# ArbPwrBoost_P3.net
KiCad netlist of a schematic drawn in Altium Designer
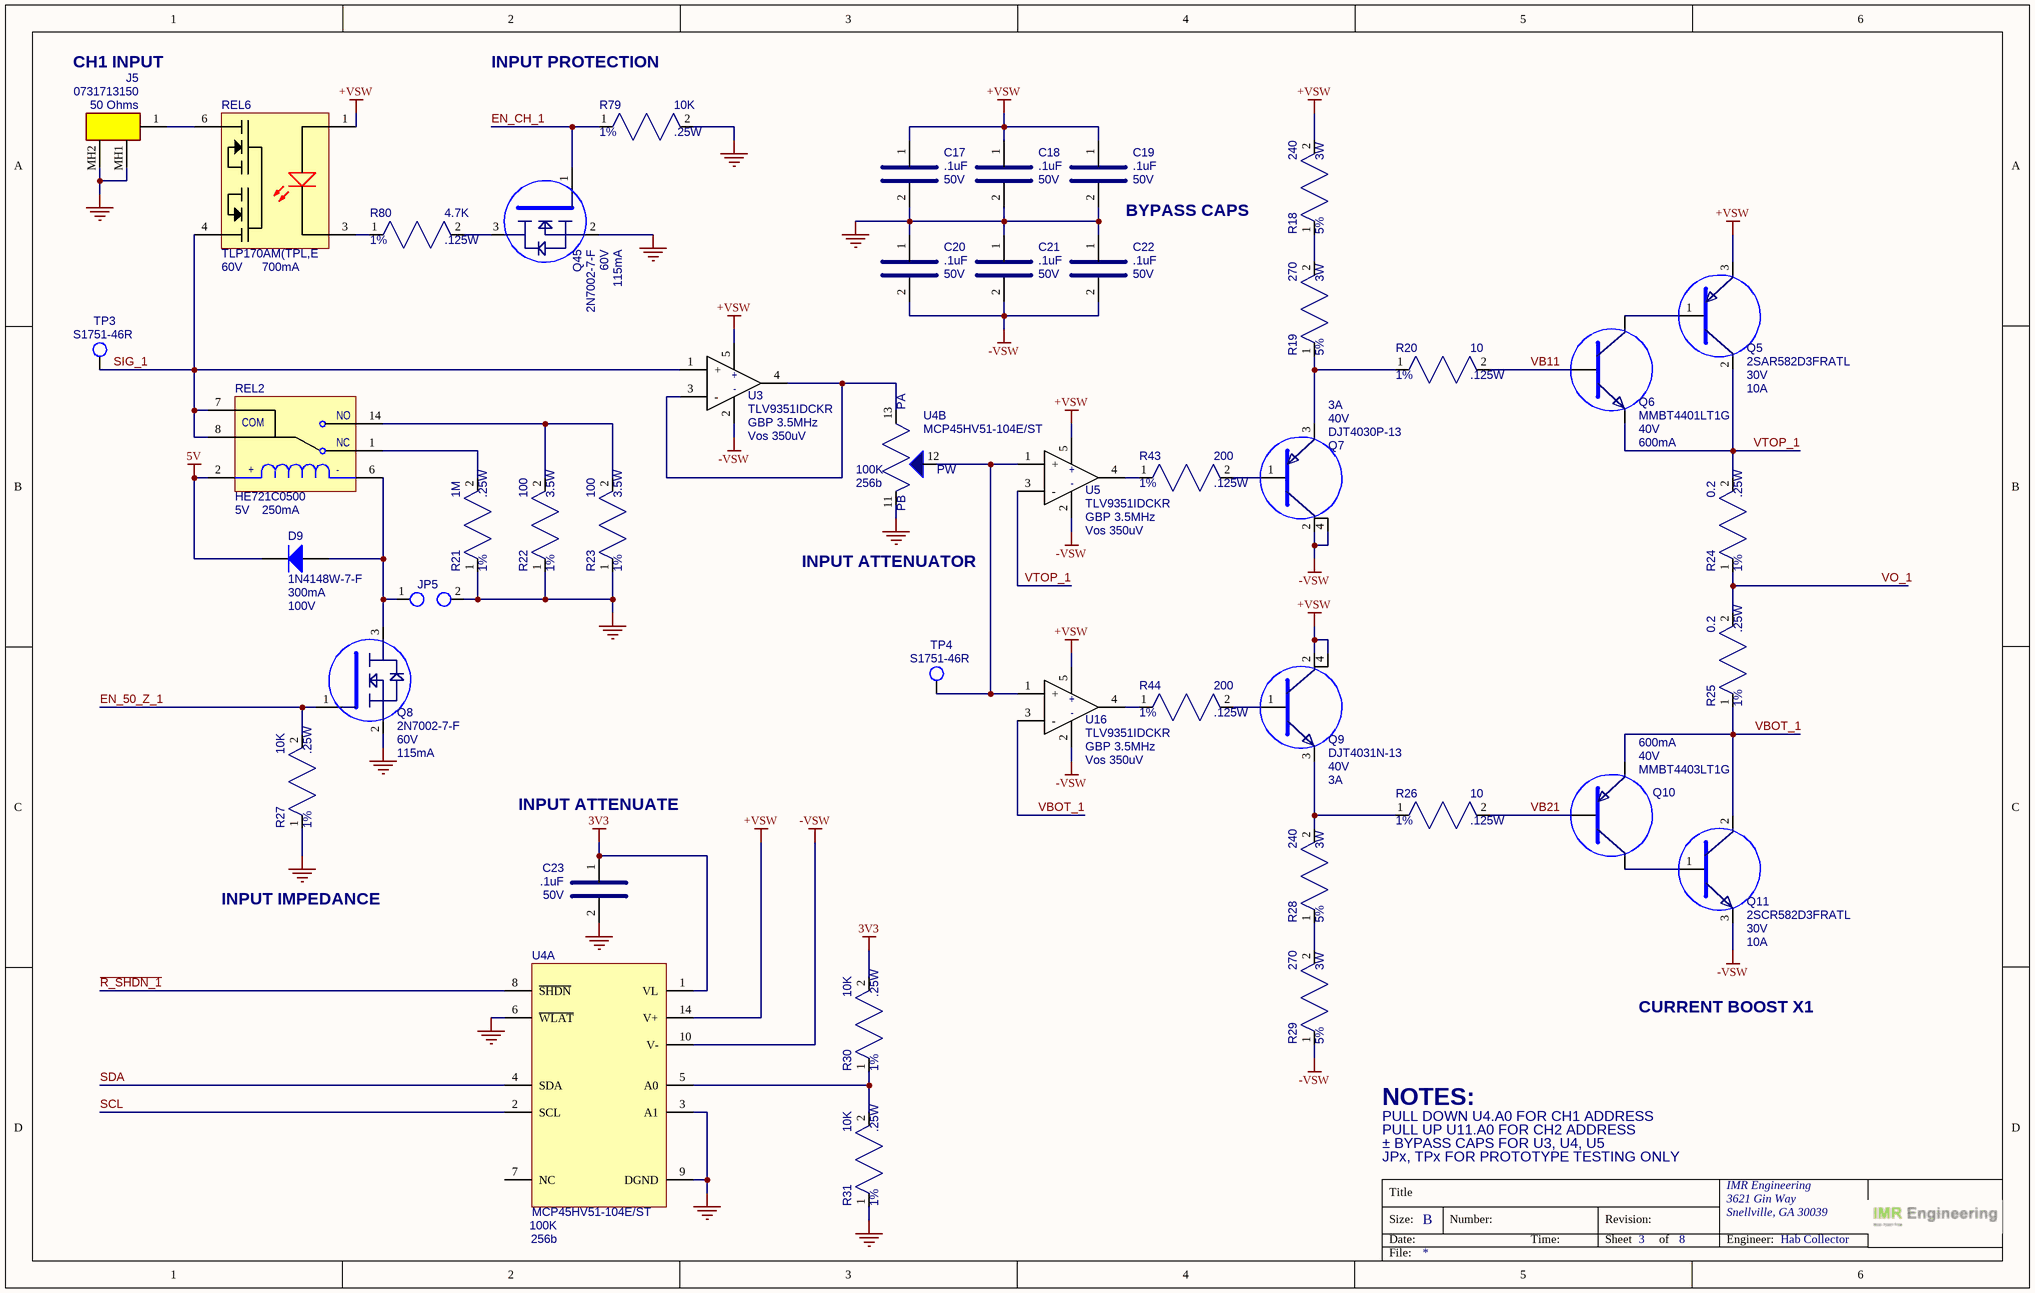
[diagram p0: ArbPwrBoost_P3.SchDoc]

(export (version "E")
  (design (tool "Eeschema 10.0.6"))
  (components
    (comp (ref "C17")
      (value ".1uF")
      (footprint "CAP_0805")
      (description "CAP CER 0.1UF 50V X7R 0805")
      (fields
        (field (name "MFG") "KYOCERA AVX")
        (field (name "VOLTAGE") "50V")
        (field (name "Comment") "KGM21NR71H104KT")
      )
      (libsource (lib "IMR_LIB_SCH_R2") (part "CAP_SMD_0.1UF_50V_0805"))
    )
    (comp (ref "C18")
      (value ".1uF")
      (footprint "CAP_0805")
      (description "CAP CER 0.1UF 50V X7R 0805")
      (fields
        (field (name "MFG") "KYOCERA AVX")
        (field (name "VOLTAGE") "50V")
        (field (name "Comment") "KGM21NR71H104KT")
      )
      (libsource (lib "IMR_LIB_SCH_R2") (part "CAP_SMD_0.1UF_50V_0805"))
    )
    (comp (ref "C19")
      (value ".1uF")
      (footprint "CAP_0805")
      (description "CAP CER 0.1UF 50V X7R 0805")
      (fields
        (field (name "MFG") "KYOCERA AVX")
        (field (name "VOLTAGE") "50V")
        (field (name "Comment") "KGM21NR71H104KT")
      )
      (libsource (lib "IMR_LIB_SCH_R2") (part "CAP_SMD_0.1UF_50V_0805"))
    )
    (comp (ref "C20")
      (value ".1uF")
      (footprint "CAP_0805")
      (description "CAP CER 0.1UF 50V X7R 0805")
      (fields
        (field (name "MFG") "KYOCERA AVX")
        (field (name "VOLTAGE") "50V")
        (field (name "Comment") "KGM21NR71H104KT")
      )
      (libsource (lib "IMR_LIB_SCH_R2") (part "CAP_SMD_0.1UF_50V_0805"))
    )
    (comp (ref "C21")
      (value ".1uF")
      (footprint "CAP_0805")
      (description "CAP CER 0.1UF 50V X7R 0805")
      (fields
        (field (name "MFG") "KYOCERA AVX")
        (field (name "VOLTAGE") "50V")
        (field (name "Comment") "KGM21NR71H104KT")
      )
      (libsource (lib "IMR_LIB_SCH_R2") (part "CAP_SMD_0.1UF_50V_0805"))
    )
    (comp (ref "C22")
      (value ".1uF")
      (footprint "CAP_0805")
      (description "CAP CER 0.1UF 50V X7R 0805")
      (fields
        (field (name "MFG") "KYOCERA AVX")
        (field (name "VOLTAGE") "50V")
        (field (name "Comment") "KGM21NR71H104KT")
      )
      (libsource (lib "IMR_LIB_SCH_R2") (part "CAP_SMD_0.1UF_50V_0805"))
    )
    (comp (ref "C23")
      (value ".1uF")
      (footprint "CAP_0805")
      (description "CAP CER 0.1UF 50V X7R 0805")
      (fields
        (field (name "MFG") "KYOCERA AVX")
        (field (name "VOLTAGE") "50V")
        (field (name "Comment") "KGM21NR71H104KT")
      )
      (libsource (lib "IMR_LIB_SCH_R2") (part "CAP_SMD_0.1UF_50V_0805"))
    )
    (comp (ref "D9")
      (value "100V")
      (footprint "SOD123")
      (description "RELAY REED SPDT 250MA 5V")
      (fields
        (field (name "MFG") "Diodes Inc")
        (field (name "MFG_PN") "1N4148W-7-F")
        (field (name "CURRENT") "300mA")
        (field (name "Comment") "1N4148W-7-F")
      )
      (libsource (lib "IMR_LIB_SCH_R2") (part "DIODE_1N4148W-7-F"))
    )
    (comp (ref "J5")
      (value "50 Ohms")
      (footprint "731713150")
      (description "CONN BNC RCPT R/A 50 OHM PCB")
      (fields
        (field (name "MFG") "Molex")
        (field (name "MFG_PN") "0731713150")
        (field (name "Comment") "0731713150")
      )
      (libsource (lib "IMR_LIB_SCH_R2") (part "CONN_MOLEX_0731713150"))
    )
    (comp (ref "JP5")
      (value "PREC002SFAN-RC")
      (footprint "HDR_1X2_100MILL")
      (description "CONN HEADER VERT 2POS 2.54MM")
      (fields (field (name "MFG") "Sullins Connector Solutions"))
      (libsource (lib "IMR_LIB_SCH_R2") (part "CONN_JUMPER_2P_100MIL_VERT"))
    )
    (comp (ref "Q5")
      (value "30V")
      (footprint "TO-252")
      (description "TRANS PNP 30V 5.7A TO-252")
      (fields
        (field (name "MFG") "Rohm Semiconductor")
        (field (name "MFG_PN") "2SAR582D3FRATL")
        (field (name "CURRENT") "10A")
        (field (name "Comment") "2SAR582D3FRATL")
      )
      (libsource (lib "IMR_LIB_SCH_R2") (part "BJT_PNP_2SAR582D3FRATL"))
    )
    (comp (ref "Q6")
      (value "40V")
      (footprint "SOT-23")
      (description "TRANS NPN 40V 0.6A SOT23-3")
      (fields
        (field (name "MFG") "On Semiconductor")
        (field (name "MFG_PN") "MMBT4401LT1G")
        (field (name "CURRENT") "600mA")
        (field (name "Comment") "MMBT4401LT1G")
      )
      (libsource (lib "IMR_LIB_SCH_R2") (part "BJT_NPN_MMBT4401LT1G"))
    )
    (comp (ref "Q7")
      (value "40V")
      (footprint "SOT223")
      (description "TRANS PNP 40V 3A SOT223")
      (fields
        (field (name "MFG") "Diodes Inc")
        (field (name "MFG_PN") "DJT4030P-13")
        (field (name "CURRENT") "3A")
        (field (name "Comment") "DJT4030P-13")
      )
      (libsource (lib "IMR_LIB_SCH_R2") (part "BJT_PNP_DJT4030P-13"))
    )
    (comp (ref "Q8")
      (value "60V")
      (footprint "SOT-23")
      (description "MOSFET N-CH 60V 115MA SOT23-3")
      (fields
        (field (name "MFG") "Diodes Inc")
        (field (name "MFG_PN") "2N7002-7-F")
        (field (name "CURRENT") "115mA")
        (field (name "Comment") "2N7002-7-F")
      )
      (libsource (lib "") (part "MOSFET_NCH_2N7002-7-F_1"))
    )
    (comp (ref "Q9")
      (value "40V")
      (footprint "SOT223")
      (description "TRANS NPN 40V 3A SOT223")
      (fields
        (field (name "MFG") "Diodes Inc")
        (field (name "MFG_PN") "DJT4031N-13")
        (field (name "CURRENT") "3A")
        (field (name "Comment") "DJT4031N-13")
      )
      (libsource (lib "IMR_LIB_SCH_R2") (part "BJT_NPN_DJT4031N-13"))
    )
    (comp (ref "Q10")
      (value "40V")
      (footprint "SOT-23")
      (description "TRANS PNP 40V 0.6A SOT23-3")
      (fields
        (field (name "MFG") "On Semiconductor")
        (field (name "MFG_PN") "MMBT4403LT1G")
        (field (name "CURRENT") "600mA")
        (field (name "Comment") "MMBT4403LT1G")
      )
      (libsource (lib "IMR_LIB_SCH_R2") (part "BJT_PNP_MMBT4403LT1G"))
    )
    (comp (ref "Q11")
      (value "30V")
      (footprint "TO-252")
      (description "TRANS NPN 30V 10A TO-252")
      (fields
        (field (name "MFG") "Rohm Semiconductor")
        (field (name "MFG_PN") "2SCR582D3FRATL")
        (field (name "CURRENT") "10A")
        (field (name "Comment") "2SCR582D3FRATL")
      )
      (libsource (lib "IMR_LIB_SCH_R2") (part "BJT_NPN_2SCR582D3FRATL"))
    )
    (comp (ref "Q45")
      (value "60V")
      (footprint "SOT-23")
      (description "MOSFET N-CH 60V 115MA SOT23-3")
      (fields
        (field (name "MFG") "Diodes Inc")
        (field (name "MFG_PN") "2N7002-7-F")
        (field (name "CURRENT") "115mA")
        (field (name "Comment") "2N7002-7-F")
      )
      (libsource (lib "IMR_LIB_SCH_R2") (part "MOSFET_NCH_2N7002-7-F"))
    )
    (comp (ref "R18")
      (value "240")
      (footprint "RES_2512")
      (description "RES 240 OHM 5% 3W 2512")
      (fields
        (field (name "MFG") "Yageo")
        (field (name "POWER") "3W")
        (field (name "TOLERANCE") "5%")
        (field (name "Comment") "RC2512JK-07240RL")
      )
      (libsource (lib "IMR_LIB_SCH_R2") (part "RES_SMD_240_2512_3W_5%"))
    )
    (comp (ref "R19")
      (value "270")
      (footprint "RES_2512")
      (description "RES 270 OHM 5% 1W 2512")
      (fields
        (field (name "MFG") "Yageo")
        (field (name "POWER") "3W")
        (field (name "TOLERANCE") "5%")
        (field (name "Comment") "RC2512JK-07270RL")
      )
      (libsource (lib "IMR_LIB_SCH_R2") (part "RES_SMD_270_2512_3W_5%"))
    )
    (comp (ref "R20")
      (value "10")
      (footprint "RES_0805")
      (description "RES SMD 10 OHM 1% 1/8W 0805")
      (fields
        (field (name "MFG") "Yageo")
        (field (name "POWER") ".125W")
        (field (name "TOLERANCE") "1%")
        (field (name "Comment") "RC0805FR-1310RL")
      )
      (libsource (lib "IMR_LIB_SCH_R2") (part "RES_SMD_10_0805_1/8W_1%"))
    )
    (comp (ref "R21")
      (value "1M")
      (footprint "RES_0805")
      (description "RES SMD 1K OHM 1% 1/4W 0805")
      (fields
        (field (name "MFG") "Yageo")
        (field (name "POWER") ".25W")
        (field (name "TOLERANCE") "1%")
        (field (name "Comment") "RC0805FR-7W1ML")
      )
      (libsource (lib "IMR_LIB_SCH_R2") (part "RES_SMD_1M_0805_1/4W_1%"))
    )
    (comp (ref "R22")
      (value "100")
      (footprint "RES_2512")
      (description "RES SMD 100 OHM 1% 3.5W 2512")
      (fields
        (field (name "MFG") "Ohmite")
        (field (name "POWER") "3.5W")
        (field (name "TOLERANCE") "1%")
        (field (name "Comment") "ALN2512F100RE-1")
      )
      (libsource (lib "IMR_LIB_SCH_R2") (part "RES_SMD_100_0805_3.5W_1%"))
    )
    (comp (ref "R23")
      (value "100")
      (footprint "RES_2512")
      (description "RES SMD 100 OHM 1% 3.5W 2512")
      (fields
        (field (name "MFG") "Ohmite")
        (field (name "POWER") "3.5W")
        (field (name "TOLERANCE") "1%")
        (field (name "Comment") "ALN2512F100RE-1")
      )
      (libsource (lib "IMR_LIB_SCH_R2") (part "RES_SMD_100_0805_3.5W_1%"))
    )
    (comp (ref "R24")
      (value "0.2")
      (footprint "RES_1206")
      (description "RES SMD 0.2 OHM 1% 1/4W 1206")
      (fields
        (field (name "MFG") "Yageo")
        (field (name "POWER") ".25W")
        (field (name "TOLERANCE") "1%")
        (field (name "Comment") "RL1206FR-070R2L")
      )
      (libsource (lib "IMR_LIB_SCH_R2") (part "RES_SMD_0.2_1206_1/4W_1%"))
    )
    (comp (ref "R25")
      (value "0.2")
      (footprint "RES_1206")
      (description "RES SMD 0.2 OHM 1% 1/4W 1206")
      (fields
        (field (name "MFG") "Yageo")
        (field (name "POWER") ".25W")
        (field (name "TOLERANCE") "1%")
        (field (name "Comment") "RL1206FR-070R2L")
      )
      (libsource (lib "IMR_LIB_SCH_R2") (part "RES_SMD_0.2_1206_1/4W_1%"))
    )
    (comp (ref "R26")
      (value "10")
      (footprint "RES_0805")
      (description "RES SMD 10 OHM 1% 1/8W 0805")
      (fields
        (field (name "MFG") "Yageo")
        (field (name "POWER") ".125W")
        (field (name "TOLERANCE") "1%")
        (field (name "Comment") "RC0805FR-1310RL")
      )
      (libsource (lib "IMR_LIB_SCH_R2") (part "RES_SMD_10_0805_1/8W_1%"))
    )
    (comp (ref "R27")
      (value "10K")
      (footprint "RES_0805")
      (description "RES SMD 10K OHM 1% 1/4W 0805")
      (fields
        (field (name "MFG") "Yageo")
        (field (name "POWER") ".25W")
        (field (name "TOLERANCE") "1%")
        (field (name "Comment") "RC0805FR-7W10KL")
      )
      (libsource (lib "IMR_LIB_SCH_R2") (part "RES_SMD_10K_0805_1/4W_1%"))
    )
    (comp (ref "R28")
      (value "240")
      (footprint "RES_2512")
      (description "RES 240 OHM 5% 3W 2512")
      (fields
        (field (name "MFG") "Yageo")
        (field (name "POWER") "3W")
        (field (name "TOLERANCE") "5%")
        (field (name "Comment") "RC2512JK-07240RL")
      )
      (libsource (lib "IMR_LIB_SCH_R2") (part "RES_SMD_240_2512_3W_5%"))
    )
    (comp (ref "R29")
      (value "270")
      (footprint "RES_2512")
      (description "RES 270 OHM 5% 1W 2512")
      (fields
        (field (name "MFG") "Yageo")
        (field (name "POWER") "3W")
        (field (name "TOLERANCE") "5%")
        (field (name "Comment") "RC2512JK-07270RL")
      )
      (libsource (lib "IMR_LIB_SCH_R2") (part "RES_SMD_270_2512_3W_5%"))
    )
    (comp (ref "R30")
      (value "10K")
      (footprint "RES_0805")
      (description "RES SMD 10K OHM 1% 1/4W 0805")
      (fields
        (field (name "MFG") "Yageo")
        (field (name "POWER") ".25W")
        (field (name "TOLERANCE") "1%")
        (field (name "Comment") "RC0805FR-7W10KL")
      )
      (libsource (lib "IMR_LIB_SCH_R2") (part "RES_SMD_10K_0805_1/4W_1%"))
    )
    (comp (ref "R31")
      (value "10K")
      (footprint "RES_0805")
      (description "RES SMD 10K OHM 1% 1/4W 0805")
      (fields
        (field (name "MFG") "Yageo")
        (field (name "POWER") ".25W")
        (field (name "TOLERANCE") "1%")
        (field (name "Comment") "RC0805FR-7W10KL")
      )
      (libsource (lib "IMR_LIB_SCH_R2") (part "RES_SMD_10K_0805_1/4W_1%"))
    )
    (comp (ref "R43")
      (value "200")
      (footprint "RES_0805")
      (description "RES SMD 200 OHM 1% 1/8W 0805")
      (fields
        (field (name "MFG") "Yageo")
        (field (name "POWER") ".125W")
        (field (name "TOLERANCE") "1%")
        (field (name "Comment") "RC0805FR-07200RL")
      )
      (libsource (lib "IMR_LIB_SCH_R2") (part "RES_SMD_200_0805_1/8W_1%"))
    )
    (comp (ref "R44")
      (value "200")
      (footprint "RES_0805")
      (description "RES SMD 200 OHM 1% 1/8W 0805")
      (fields
        (field (name "MFG") "Yageo")
        (field (name "POWER") ".125W")
        (field (name "TOLERANCE") "1%")
        (field (name "Comment") "RC0805FR-07200RL")
      )
      (libsource (lib "IMR_LIB_SCH_R2") (part "RES_SMD_200_0805_1/8W_1%"))
    )
    (comp (ref "R79")
      (value "10K")
      (footprint "RES_0805")
      (description "RES SMD 10K OHM 1% 1/4W 0805")
      (fields
        (field (name "MFG") "Yageo")
        (field (name "POWER") ".25W")
        (field (name "TOLERANCE") "1%")
        (field (name "Comment") "RC0805FR-7W10KL")
      )
      (libsource (lib "IMR_LIB_SCH_R2") (part "RES_SMD_10K_0805_1/4W_1%"))
    )
    (comp (ref "R80")
      (value "4.7K")
      (footprint "RES_0805")
      (description "RES SMD 4.7K OHM 1% 1/8W 0805")
      (fields
        (field (name "MFG") "Yageo")
        (field (name "POWER") ".125W")
        (field (name "TOLERANCE") "1%")
        (field (name "Comment") "RC0805FR-134K7L")
      )
      (libsource (lib "IMR_LIB_SCH_R2") (part "RES_SMD_4.7K_0805_1/8W_1%"))
    )
    (comp (ref "REL2")
      (value "5V")
      (footprint "HE700")
      (description "RELAY REED SPDT 250MA 5V")
      (fields
        (field (name "MFG") "Littlefuse")
        (field (name "MFG_PN") "HE721C0500")
        (field (name "CURRENT") "250mA")
        (field (name "Comment") "HE721C0500")
      )
      (libsource (lib "IMR_LIB_SCH_R2") (part "RELAY_HE721C0500"))
    )
    (comp (ref "REL6")
      (value "60V")
      (footprint "SOP-6")
      (description "SSR RELAY SPST-NO 700MA 0-60V")
      (fields
        (field (name "MFG") "Toshiba")
        (field (name "MFG_PN") "TLP170AM(TPL,E")
        (field (name "CURRENT") "700mA")
        (field (name "Comment") "TLP170AM(TPL,E")
      )
      (libsource (lib "IMR_LIB_SCH_R2") (part "RELAY_TLP170AM(TPL,E"))
    )
    (comp (ref "TP3")
      (value "S1751-46R")
      (footprint "HARWIN_S1751")
      (description "PCB TEST POINT CONNECT")
      (fields (field (name "MFG") "Harwin Inc") (field (name "MFG_PN") "S1751-46R"))
      (libsource (lib "IMR_LIB_SCH_R2") (part "CONN_TEST_POINT_S1751-46R"))
    )
    (comp (ref "TP4")
      (value "S1751-46R")
      (footprint "HARWIN_S1751")
      (description "PCB TEST POINT CONNECT")
      (fields (field (name "MFG") "Harwin Inc") (field (name "MFG_PN") "S1751-46R"))
      (libsource (lib "IMR_LIB_SCH_R2") (part "CONN_TEST_POINT_S1751-46R"))
    )
    (comp (ref "U3")
      (value "GBP 3.5MHz")
      (footprint "SOT-353")
      (description "IC OPAMP GP 3.5MHZ 350uV C70-5")
      (fields
        (field (name "MFG") "Texas Instruments")
        (field (name "MFG_PN") "TLV9351IDCKR")
        (field (name "VOS") "Vos 350uV")
        (field (name "Comment") "TLV9351IDCKR")
      )
      (libsource (lib "IMR_LIB_SCH_R2") (part "OPAMP_TLV9351IDCKR"))
    )
    (comp (ref "U4")
      (value "100K")
      (footprint "TSSOP-14")
      (description "IC DGT POT 100KOHM 256TP 14TSSOP")
      (fields
        (field (name "MFG") "Microchip")
        (field (name "MFG_PN") "MCP45HV51-104E/ST")
        (field (name "TAP") "256b")
        (field (name "Comment") "MCP45HV51-104E/ST")
      )
      (libsource (lib "IMR_LIB_SCH_R2") (part "IC_MCP45HV51-104E/ST"))
    )
    (comp (ref "U5")
      (value "GBP 3.5MHz")
      (footprint "SOT-353")
      (description "IC OPAMP GP 3.5MHZ 350uV C70-5")
      (fields
        (field (name "MFG") "Texas Instruments")
        (field (name "MFG_PN") "TLV9351IDCKR")
        (field (name "VOS") "Vos 350uV")
        (field (name "Comment") "TLV9351IDCKR")
      )
      (libsource (lib "IMR_LIB_SCH_R2") (part "OPAMP_TLV9351IDCKR"))
    )
    (comp (ref "U16")
      (value "GBP 3.5MHz")
      (footprint "SOT-353")
      (description "IC OPAMP GP 3.5MHZ 350uV C70-5")
      (fields
        (field (name "MFG") "Texas Instruments")
        (field (name "MFG_PN") "TLV9351IDCKR")
        (field (name "VOS") "Vos 350uV")
        (field (name "Comment") "TLV9351IDCKR")
      )
      (libsource (lib "IMR_LIB_SCH_R2") (part "OPAMP_TLV9351IDCKR"))
    )
  )
  (nets
    (net (code "1") (name "+VSW") (class "Default")
      (node (ref "C17") (pin "1") (pinfunction "1_1") (pintype "passive"))
      (node (ref "C18") (pin "1") (pinfunction "1_1") (pintype "passive"))
      (node (ref "C19") (pin "1") (pinfunction "1_1") (pintype "passive"))
      (node (ref "Q5") (pin "3") (pinfunction "E_3") (pintype "passive"))
      (node (ref "Q9") (pin "2") (pinfunction "C_2") (pintype "passive"))
      (node (ref "Q9") (pin "4") (pinfunction "C_4") (pintype "passive"))
      (node (ref "R18") (pin "2") (pinfunction "2_2") (pintype "passive"))
      (node (ref "REL6") (pin "1") (pinfunction "1_1") (pintype "passive"))
      (node (ref "U16") (pin "5") (pintype "passive"))
      (node (ref "U3") (pin "5") (pintype "passive"))
      (node (ref "U4") (pin "14") (pinfunction "V+_14") (pintype "passive"))
      (node (ref "U5") (pin "5") (pintype "passive"))
    )
    (net (code "2") (name "-VSW") (class "Default")
      (node (ref "C20") (pin "2") (pinfunction "2_2") (pintype "passive"))
      (node (ref "C21") (pin "2") (pinfunction "2_2") (pintype "passive"))
      (node (ref "C22") (pin "2") (pinfunction "2_2") (pintype "passive"))
      (node (ref "Q11") (pin "3") (pinfunction "E_3") (pintype "passive"))
      (node (ref "Q7") (pin "2") (pinfunction "C_2") (pintype "passive"))
      (node (ref "Q7") (pin "4") (pinfunction "C_4") (pintype "passive"))
      (node (ref "R29") (pin "1") (pinfunction "1_1") (pintype "passive"))
      (node (ref "U16") (pin "2") (pintype "passive"))
      (node (ref "U3") (pin "2") (pintype "passive"))
      (node (ref "U4") (pin "10") (pinfunction "V-_10") (pintype "passive"))
      (node (ref "U5") (pin "2") (pintype "passive"))
    )
    (net (code "3") (name "/EN_50_Z_1") (class "Default")
      (node (ref "Q8") (pin "1") (pinfunction "B_1") (pintype "passive"))
      (node (ref "R27") (pin "2") (pinfunction "2_2") (pintype "passive"))
    )
    (net (code "4") (name "/EN_CH_1") (class "Default")
      (node (ref "Q45") (pin "1") (pinfunction "B_1") (pintype "passive"))
      (node (ref "R79") (pin "1") (pinfunction "1_1") (pintype "passive"))
    )
    (net (code "5") (name "/SCL") (class "Default")
      (node (ref "U4") (pin "2") (pinfunction "SCL_2") (pintype "passive"))
    )
    (net (code "6") (name "/SDA") (class "Default")
      (node (ref "U4") (pin "4") (pinfunction "SDA_4") (pintype "passive"))
    )
    (net (code "7") (name "/SIG_1") (class "Default")
      (node (ref "REL2") (pin "7") (pinfunction "COM_7") (pintype "passive"))
      (node (ref "REL2") (pin "8") (pinfunction "COM_8") (pintype "passive"))
      (node (ref "REL6") (pin "4") (pinfunction "4_4") (pintype "passive"))
      (node (ref "TP3") (pin "1") (pintype "passive"))
      (node (ref "U3") (pin "1") (pinfunction "+_1") (pintype "passive"))
    )
    (net (code "8") (name "/VB11") (class "Default")
      (node (ref "Q6") (pin "1") (pinfunction "B_1") (pintype "passive"))
      (node (ref "R20") (pin "2") (pinfunction "2_2") (pintype "passive"))
    )
    (net (code "9") (name "/VB21") (class "Default")
      (node (ref "Q10") (pin "1") (pinfunction "B_1") (pintype "passive"))
      (node (ref "R26") (pin "2") (pinfunction "2_2") (pintype "passive"))
    )
    (net (code "10") (name "/VBOT_1") (class "Default")
      (node (ref "Q10") (pin "2") (pinfunction "E_2") (pintype "passive"))
      (node (ref "Q11") (pin "2") (pinfunction "C_2") (pintype "passive"))
      (node (ref "R25") (pin "1") (pinfunction "1_1") (pintype "passive"))
      (node (ref "U16") (pin "3") (pinfunction "-_3") (pintype "passive"))
    )
    (net (code "11") (name "/VO_1") (class "Default")
      (node (ref "R24") (pin "1") (pinfunction "1_1") (pintype "passive"))
      (node (ref "R25") (pin "2") (pinfunction "2_2") (pintype "passive"))
    )
    (net (code "12") (name "/VTOP_1") (class "Default")
      (node (ref "Q5") (pin "2") (pinfunction "C_2") (pintype "passive"))
      (node (ref "Q6") (pin "2") (pinfunction "E_2") (pintype "passive"))
      (node (ref "R24") (pin "2") (pinfunction "2_2") (pintype "passive"))
      (node (ref "U5") (pin "3") (pinfunction "-_3") (pintype "passive"))
    )
    (net (code "13") (name "/~{R_SHDN_1}") (class "Default")
      (node (ref "U4") (pin "8") (pinfunction "~{SHDN}_8") (pintype "passive"))
    )
    (net (code "14") (name "3V3") (class "Default")
      (node (ref "C23") (pin "1") (pinfunction "1_1") (pintype "passive"))
      (node (ref "R30") (pin "2") (pinfunction "2_2") (pintype "passive"))
      (node (ref "U4") (pin "1") (pinfunction "VL_1") (pintype "passive"))
    )
    (net (code "15") (name "5V") (class "Default")
      (node (ref "D9") (pin "2") (pinfunction "K_2") (pintype "passive"))
      (node (ref "REL2") (pin "2") (pintype "passive"))
    )
    (net (code "16") (name "GND") (class "Default")
      (node (ref "C17") (pin "2") (pinfunction "2_2") (pintype "passive"))
      (node (ref "C18") (pin "2") (pinfunction "2_2") (pintype "passive"))
      (node (ref "C19") (pin "2") (pinfunction "2_2") (pintype "passive"))
      (node (ref "C20") (pin "1") (pinfunction "1_1") (pintype "passive"))
      (node (ref "C21") (pin "1") (pinfunction "1_1") (pintype "passive"))
      (node (ref "C22") (pin "1") (pinfunction "1_1") (pintype "passive"))
      (node (ref "C23") (pin "2") (pinfunction "2_2") (pintype "passive"))
      (node (ref "J5") (pin "MH1") (pintype "passive"))
      (node (ref "J5") (pin "MH2") (pintype "passive"))
      (node (ref "JP5") (pin "2") (pintype "passive"))
      (node (ref "Q45") (pin "2") (pinfunction "E_2") (pintype "passive"))
      (node (ref "Q8") (pin "2") (pinfunction "E_2") (pintype "passive"))
      (node (ref "R21") (pin "1") (pinfunction "1_1") (pintype "passive"))
      (node (ref "R22") (pin "1") (pinfunction "1_1") (pintype "passive"))
      (node (ref "R23") (pin "1") (pinfunction "1_1") (pintype "passive"))
      (node (ref "R27") (pin "1") (pinfunction "1_1") (pintype "passive"))
      (node (ref "R31") (pin "1") (pinfunction "1_1") (pintype "passive"))
      (node (ref "R79") (pin "2") (pinfunction "2_2") (pintype "passive"))
      (node (ref "U4") (pin "11") (pinfunction "PB0_11") (pintype "passive"))
      (node (ref "U4") (pin "3") (pinfunction "A1_3") (pintype "passive"))
      (node (ref "U4") (pin "6") (pinfunction "~{WLAT}_6") (pintype "passive"))
      (node (ref "U4") (pin "9") (pinfunction "DGND_9") (pintype "passive"))
    )
    (net (code "17") (name "Net-(D9-A)") (class "Default")
      (node (ref "D9") (pin "1") (pinfunction "A_1") (pintype "passive"))
      (node (ref "JP5") (pin "1") (pintype "passive"))
      (node (ref "Q8") (pin "3") (pinfunction "C_3") (pintype "passive"))
      (node (ref "REL2") (pin "6") (pintype "passive"))
    )
    (net (code "18") (name "Net-(J5-Pad1)") (class "Default")
      (node (ref "J5") (pin "1") (pintype "passive"))
      (node (ref "REL6") (pin "6") (pinfunction "6_6") (pintype "passive"))
    )
    (net (code "19") (name "Net-(Q5-B)") (class "Default")
      (node (ref "Q5") (pin "1") (pinfunction "B_1") (pintype "passive"))
      (node (ref "Q6") (pin "3") (pinfunction "C_3") (pintype "passive"))
    )
    (net (code "20") (name "Net-(Q7-B)") (class "Default")
      (node (ref "Q7") (pin "1") (pinfunction "B_1") (pintype "passive"))
      (node (ref "R43") (pin "2") (pinfunction "2_2") (pintype "passive"))
    )
    (net (code "21") (name "Net-(Q7-E)") (class "Default")
      (node (ref "Q7") (pin "3") (pinfunction "E_3") (pintype "passive"))
      (node (ref "R19") (pin "1") (pinfunction "1_1") (pintype "passive"))
      (node (ref "R20") (pin "1") (pinfunction "1_1") (pintype "passive"))
    )
    (net (code "22") (name "Net-(Q9-B)") (class "Default")
      (node (ref "Q9") (pin "1") (pinfunction "B_1") (pintype "passive"))
      (node (ref "R44") (pin "2") (pinfunction "2_2") (pintype "passive"))
    )
    (net (code "23") (name "Net-(Q9-E)") (class "Default")
      (node (ref "Q9") (pin "3") (pinfunction "E_3") (pintype "passive"))
      (node (ref "R26") (pin "1") (pinfunction "1_1") (pintype "passive"))
      (node (ref "R28") (pin "2") (pinfunction "2_2") (pintype "passive"))
    )
    (net (code "24") (name "Net-(Q10-C)") (class "Default")
      (node (ref "Q10") (pin "3") (pinfunction "C_3") (pintype "passive"))
      (node (ref "Q11") (pin "1") (pinfunction "B_1") (pintype "passive"))
    )
    (net (code "25") (name "Net-(Q45-C)") (class "Default")
      (node (ref "Q45") (pin "3") (pinfunction "C_3") (pintype "passive"))
      (node (ref "R80") (pin "2") (pinfunction "2_2") (pintype "passive"))
    )
    (net (code "26") (name "Net-(R18-Pad1)") (class "Default")
      (node (ref "R18") (pin "1") (pinfunction "1_1") (pintype "passive"))
      (node (ref "R19") (pin "2") (pinfunction "2_2") (pintype "passive"))
    )
    (net (code "27") (name "Net-(R28-Pad1)") (class "Default")
      (node (ref "R28") (pin "1") (pinfunction "1_1") (pintype "passive"))
      (node (ref "R29") (pin "2") (pinfunction "2_2") (pintype "passive"))
    )
    (net (code "28") (name "Net-(R43-Pad1)") (class "Default")
      (node (ref "R43") (pin "1") (pinfunction "1_1") (pintype "passive"))
      (node (ref "U5") (pin "4") (pintype "passive"))
    )
    (net (code "29") (name "Net-(R44-Pad1)") (class "Default")
      (node (ref "R44") (pin "1") (pinfunction "1_1") (pintype "passive"))
      (node (ref "U16") (pin "4") (pintype "passive"))
    )
    (net (code "30") (name "Net-(R80-Pad1)") (class "Default")
      (node (ref "R80") (pin "1") (pinfunction "1_1") (pintype "passive"))
      (node (ref "REL6") (pin "3") (pinfunction "3_3") (pintype "passive"))
    )
    (net (code "31") (name "Net-(REL2-NC)") (class "Default")
      (node (ref "R21") (pin "2") (pinfunction "2_2") (pintype "passive"))
      (node (ref "REL2") (pin "1") (pinfunction "NC_1") (pintype "passive"))
    )
    (net (code "32") (name "Net-(REL2-NO)") (class "Default")
      (node (ref "R22") (pin "2") (pinfunction "2_2") (pintype "passive"))
      (node (ref "R23") (pin "2") (pinfunction "2_2") (pintype "passive"))
      (node (ref "REL2") (pin "14") (pinfunction "NO_14") (pintype "passive"))
    )
    (net (code "33") (name "Net-(U3--)") (class "Default")
      (node (ref "U3") (pin "3") (pinfunction "-_3") (pintype "passive"))
      (node (ref "U3") (pin "4") (pintype "passive"))
      (node (ref "U4") (pin "13") (pinfunction "PA_13") (pintype "passive"))
    )
    (net (code "34") (name "Net-(U4A-A0)") (class "Default")
      (node (ref "R30") (pin "1") (pinfunction "1_1") (pintype "passive"))
      (node (ref "R31") (pin "2") (pinfunction "2_2") (pintype "passive"))
      (node (ref "U4") (pin "5") (pinfunction "A0_5") (pintype "passive"))
    )
    (net (code "35") (name "Net-(U16-+)") (class "Default")
      (node (ref "TP4") (pin "1") (pintype "passive"))
      (node (ref "U16") (pin "1") (pinfunction "+_1") (pintype "passive"))
      (node (ref "U4") (pin "12") (pinfunction "PW0_12") (pintype "passive"))
      (node (ref "U5") (pin "1") (pinfunction "+_1") (pintype "passive"))
    )
    (net (code "36") (name "unconnected-(U4A-NC-Pad7)") (class "Default")
      (node (ref "U4") (pin "7") (pinfunction "NC_7") (pintype "passive"))
    )
  )
)
